# Power.net
KiCad netlist of a schematic drawn in Altium Designer
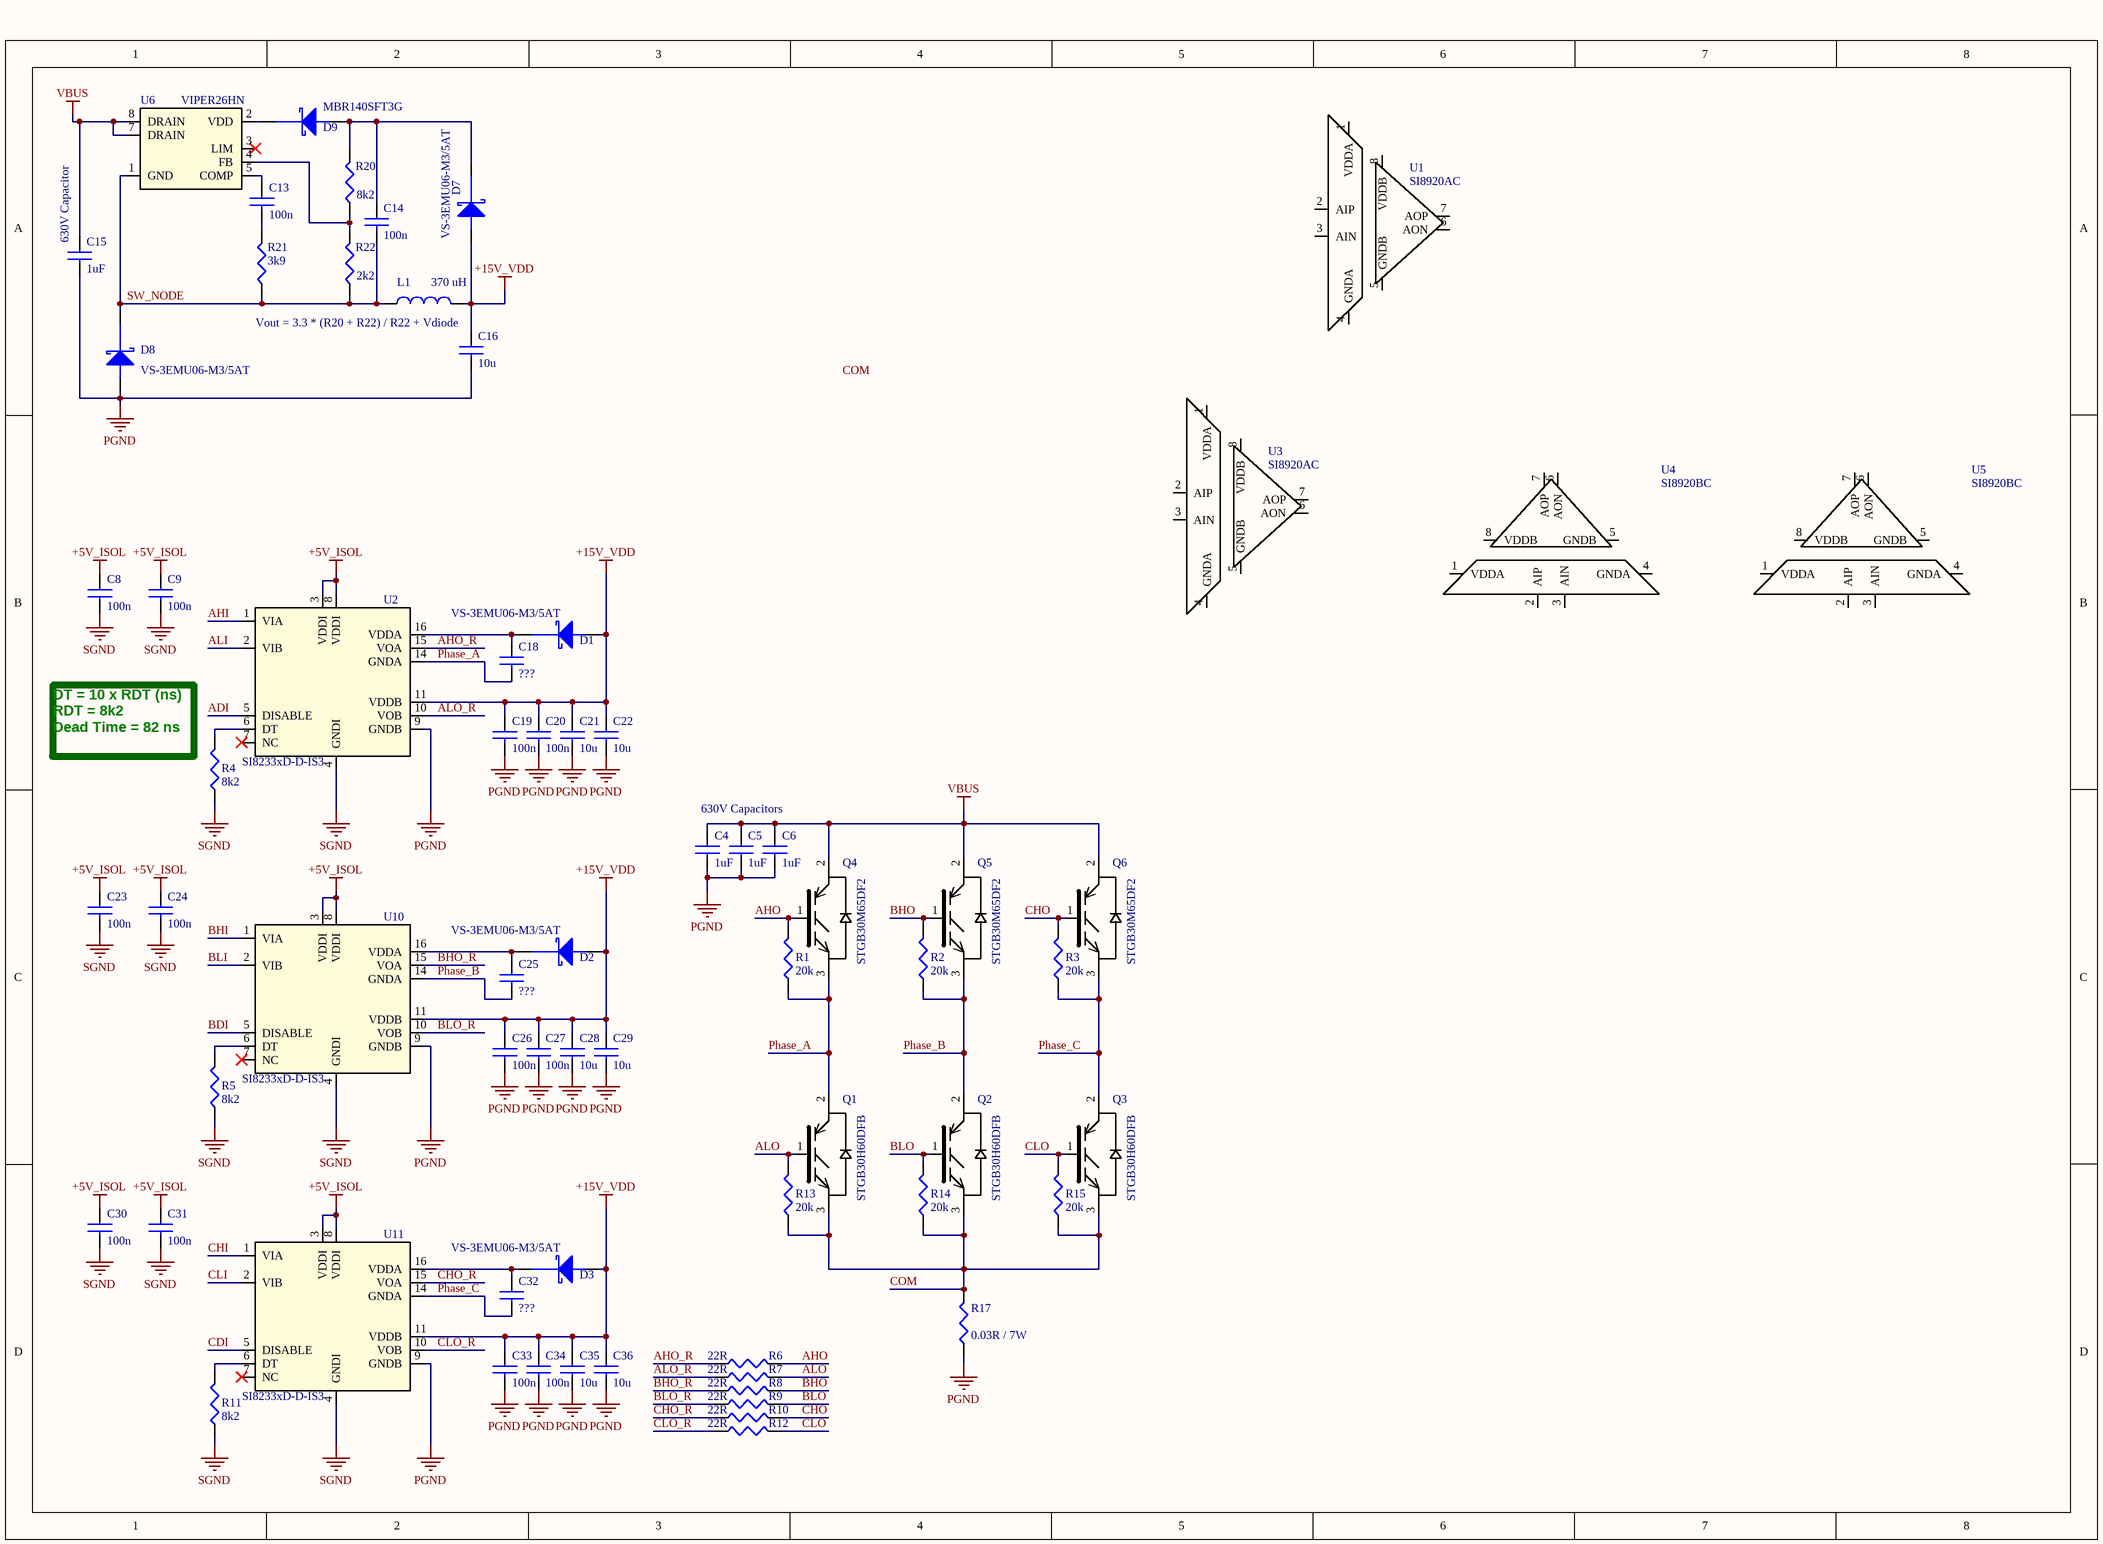
[diagram p0: Power.SchDoc]

(export (version "E")
  (design (tool "Eeschema 10.0.6"))
  (components
    (comp (ref "C4")
      (value "1uF")
      (footprint "AllogicaDisk_PcbLib:C_HIGH_V")
      (description "CAP CER 1UF 630V X7T STACKED SMD")
      (fields
        (field (name "MANUFACTURER") "Murata Electronics North America")
        (field (name "MANUFACTURER PART NUMBER") "KC355TD7LQ105MV01K")
      )
      (libsource (lib "AllogicaDisk_SchLib") (part "CAP_HIGH_VOLAGE"))
    )
    (comp (ref "C5")
      (value "1uF")
      (footprint "AllogicaDisk_PcbLib:C_HIGH_V")
      (description "CAP CER 1UF 630V X7T STACKED SMD")
      (fields
        (field (name "MANUFACTURER") "Murata Electronics North America")
        (field (name "MANUFACTURER PART NUMBER") "KC355TD7LQ105MV01K")
      )
      (libsource (lib "AllogicaDisk_SchLib") (part "CAP_HIGH_VOLAGE"))
    )
    (comp (ref "C6")
      (value "1uF")
      (footprint "AllogicaDisk_PcbLib:C_HIGH_V")
      (description "CAP CER 1UF 630V X7T STACKED SMD")
      (fields
        (field (name "MANUFACTURER") "Murata Electronics North America")
        (field (name "MANUFACTURER PART NUMBER") "KC355TD7LQ105MV01K")
      )
      (libsource (lib "AllogicaDisk_SchLib") (part "CAP_HIGH_VOLAGE"))
    )
    (comp (ref "C8")
      (value "100n")
      (footprint "AllogicaDisk_PcbLib:C0805")
      (description "0805 Capacitor")
      (libsource (lib "AllogicaDisk_SchLib") (part "CAP_0805"))
    )
    (comp (ref "C9")
      (value "100n")
      (footprint "AllogicaDisk_PcbLib:C0805")
      (description "0805 Capacitor")
      (libsource (lib "AllogicaDisk_SchLib") (part "CAP_0805"))
    )
    (comp (ref "C13")
      (value "100n")
      (footprint "AllogicaDisk_PcbLib:C0805")
      (description "0805 Capacitor")
      (libsource (lib "AllogicaDisk_SchLib") (part "CAP_0805"))
    )
    (comp (ref "C14")
      (value "100n")
      (footprint "AllogicaDisk_PcbLib:C0805")
      (description "0805 Capacitor")
      (libsource (lib "AllogicaDisk_SchLib") (part "CAP_0805"))
    )
    (comp (ref "C15")
      (value "1uF")
      (footprint "AllogicaDisk_PcbLib:C_HIGH_V")
      (description "CAP CER 1UF 630V X7T STACKED SMD")
      (fields
        (field (name "MANUFACTURER") "Murata Electronics North America")
        (field (name "MANUFACTURER PART NUMBER") "KC355TD7LQ105MV01K")
      )
      (libsource (lib "AllogicaDisk_SchLib") (part "CAP_HIGH_VOLAGE"))
    )
    (comp (ref "C16")
      (value "10u")
      (footprint "AllogicaDisk_PcbLib:C1206")
      (description "CAP CER 10UF 35V X5R 1206")
      (fields (field (name "TOLERANCE") "±20%") (field (name "MANUFACTURER") "Murata"))
      (libsource (lib "AllogicaDisk_SchLib") (part "CAP_1206_10u"))
    )
    (comp (ref "C18")
      (value "???")
      (footprint "AllogicaDisk_PcbLib:C0805")
      (description "0805 Capacitor")
      (libsource (lib "AllogicaDisk_SchLib") (part "CAP_0805"))
    )
    (comp (ref "C19")
      (value "100n")
      (footprint "AllogicaDisk_PcbLib:C0805")
      (description "0805 Capacitor")
      (libsource (lib "AllogicaDisk_SchLib") (part "CAP_0805"))
    )
    (comp (ref "C20")
      (value "100n")
      (footprint "AllogicaDisk_PcbLib:C0805")
      (description "0805 Capacitor")
      (libsource (lib "AllogicaDisk_SchLib") (part "CAP_0805"))
    )
    (comp (ref "C21")
      (value "10u")
      (footprint "AllogicaDisk_PcbLib:C0805")
      (description "0805 Capacitor")
      (libsource (lib "AllogicaDisk_SchLib") (part "CAP_0805"))
    )
    (comp (ref "C22")
      (value "10u")
      (footprint "AllogicaDisk_PcbLib:C0805")
      (description "0805 Capacitor")
      (libsource (lib "AllogicaDisk_SchLib") (part "CAP_0805"))
    )
    (comp (ref "C23")
      (value "100n")
      (footprint "AllogicaDisk_PcbLib:C0805")
      (description "0805 Capacitor")
      (libsource (lib "AllogicaDisk_SchLib") (part "CAP_0805"))
    )
    (comp (ref "C24")
      (value "100n")
      (footprint "AllogicaDisk_PcbLib:C0805")
      (description "0805 Capacitor")
      (libsource (lib "AllogicaDisk_SchLib") (part "CAP_0805"))
    )
    (comp (ref "C25")
      (value "???")
      (footprint "AllogicaDisk_PcbLib:C0805")
      (description "0805 Capacitor")
      (libsource (lib "AllogicaDisk_SchLib") (part "CAP_0805"))
    )
    (comp (ref "C26")
      (value "100n")
      (footprint "AllogicaDisk_PcbLib:C0805")
      (description "0805 Capacitor")
      (libsource (lib "AllogicaDisk_SchLib") (part "CAP_0805"))
    )
    (comp (ref "C27")
      (value "100n")
      (footprint "AllogicaDisk_PcbLib:C0805")
      (description "0805 Capacitor")
      (libsource (lib "AllogicaDisk_SchLib") (part "CAP_0805"))
    )
    (comp (ref "C28")
      (value "10u")
      (footprint "AllogicaDisk_PcbLib:C0805")
      (description "0805 Capacitor")
      (libsource (lib "AllogicaDisk_SchLib") (part "CAP_0805"))
    )
    (comp (ref "C29")
      (value "10u")
      (footprint "AllogicaDisk_PcbLib:C0805")
      (description "0805 Capacitor")
      (libsource (lib "AllogicaDisk_SchLib") (part "CAP_0805"))
    )
    (comp (ref "C30")
      (value "100n")
      (footprint "AllogicaDisk_PcbLib:C0805")
      (description "0805 Capacitor")
      (libsource (lib "AllogicaDisk_SchLib") (part "CAP_0805"))
    )
    (comp (ref "C31")
      (value "100n")
      (footprint "AllogicaDisk_PcbLib:C0805")
      (description "0805 Capacitor")
      (libsource (lib "AllogicaDisk_SchLib") (part "CAP_0805"))
    )
    (comp (ref "C32")
      (value "???")
      (footprint "AllogicaDisk_PcbLib:C0805")
      (description "0805 Capacitor")
      (libsource (lib "AllogicaDisk_SchLib") (part "CAP_0805"))
    )
    (comp (ref "C33")
      (value "100n")
      (footprint "AllogicaDisk_PcbLib:C0805")
      (description "0805 Capacitor")
      (libsource (lib "AllogicaDisk_SchLib") (part "CAP_0805"))
    )
    (comp (ref "C34")
      (value "100n")
      (footprint "AllogicaDisk_PcbLib:C0805")
      (description "0805 Capacitor")
      (libsource (lib "AllogicaDisk_SchLib") (part "CAP_0805"))
    )
    (comp (ref "C35")
      (value "10u")
      (footprint "AllogicaDisk_PcbLib:C0805")
      (description "0805 Capacitor")
      (libsource (lib "AllogicaDisk_SchLib") (part "CAP_0805"))
    )
    (comp (ref "C36")
      (value "10u")
      (footprint "AllogicaDisk_PcbLib:C0805")
      (description "0805 Capacitor")
      (libsource (lib "AllogicaDisk_SchLib") (part "CAP_0805"))
    )
    (comp (ref "D1")
      (value "VS-3EMU06-M3/5AT")
      (footprint "AllogicaDisk_PcbLib:DO-214AC")
      (description "DIODE GEN PURP 600V 3A DO214AC")
      (fields (field (name "MANUFACTURER") "Vishay Semiconductor Diodes Division"))
      (libsource (lib "AllogicaDisk_SchLib") (part "VS-3EMU06-M3/5AT"))
    )
    (comp (ref "D2")
      (value "VS-3EMU06-M3/5AT")
      (footprint "AllogicaDisk_PcbLib:DO-214AC")
      (description "DIODE GEN PURP 600V 3A DO214AC")
      (fields (field (name "MANUFACTURER") "Vishay Semiconductor Diodes Division"))
      (libsource (lib "AllogicaDisk_SchLib") (part "VS-3EMU06-M3/5AT"))
    )
    (comp (ref "D3")
      (value "VS-3EMU06-M3/5AT")
      (footprint "AllogicaDisk_PcbLib:DO-214AC")
      (description "DIODE GEN PURP 600V 3A DO214AC")
      (fields (field (name "MANUFACTURER") "Vishay Semiconductor Diodes Division"))
      (libsource (lib "AllogicaDisk_SchLib") (part "VS-3EMU06-M3/5AT"))
    )
    (comp (ref "D7")
      (value "VS-3EMU06-M3/5AT")
      (footprint "AllogicaDisk_PcbLib:DO-214AC")
      (description "DIODE GEN PURP 600V 3A DO214AC")
      (fields (field (name "MANUFACTURER") "Vishay Semiconductor Diodes Division"))
      (libsource (lib "AllogicaDisk_SchLib") (part "VS-3EMU06-M3/5AT"))
    )
    (comp (ref "D8")
      (value "VS-3EMU06-M3/5AT")
      (footprint "AllogicaDisk_PcbLib:DO-214AC")
      (description "DIODE GEN PURP 600V 3A DO214AC")
      (fields (field (name "MANUFACTURER") "Vishay Semiconductor Diodes Division"))
      (libsource (lib "AllogicaDisk_SchLib") (part "VS-3EMU06-M3/5AT"))
    )
    (comp (ref "D9")
      (value "MBR140SFT3G")
      (footprint "AllogicaDisk_PcbLib:SOD-123FL")
      (description "DIODE SCHOTTKY 550mV @ 1A, 40V, SOD123L")
      (fields
        (field (name "MANUFACTURER") "ON Semiconductor")
        (field (name "MANUFACTURER PART NUMBER") "MBR140SFT1G")
      )
      (libsource (lib "AllogicaDisk_SchLib") (part "MBR140SFT3G"))
    )
    (comp (ref "L1")
      (value "370 uH")
      (footprint "AllogicaDisk_PcbLib:IND_370u")
      (description "390µH Shielded Wirewound Inductor 1.6A 680 mOhm Max Nonstandard")
      (fields
        (field (name "MANUFACTURER") "Bourns Inc.")
        (field (name "MANUFACTURER PART NUMBER") "PM127SH-391M-RC")
      )
      (libsource (lib "AllogicaDisk_SchLib") (part "IND_370u"))
    )
    (comp (ref "Q1")
      (value "STGB30H60DFB")
      (footprint "AllogicaDisk_PcbLib:D2PAK")
      (description "TRENCH GATE FIELD-STOP IGBT, HB")
      (fields (field (name "MANUFACTURER") "STMicroelectronics"))
      (libsource (lib "AllogicaDisk_SchLib") (part "STGB30H60DFB"))
    )
    (comp (ref "Q2")
      (value "STGB30H60DFB")
      (footprint "AllogicaDisk_PcbLib:D2PAK")
      (description "TRENCH GATE FIELD-STOP IGBT, HB")
      (fields (field (name "MANUFACTURER") "STMicroelectronics"))
      (libsource (lib "AllogicaDisk_SchLib") (part "STGB30H60DFB"))
    )
    (comp (ref "Q3")
      (value "STGB30H60DFB")
      (footprint "AllogicaDisk_PcbLib:D2PAK")
      (description "TRENCH GATE FIELD-STOP IGBT, HB")
      (fields (field (name "MANUFACTURER") "STMicroelectronics"))
      (libsource (lib "AllogicaDisk_SchLib") (part "STGB30H60DFB"))
    )
    (comp (ref "Q4")
      (value "STGB30M65DF2")
      (footprint "AllogicaDisk_PcbLib:D2PAK")
      (description "IGBT 650V 30A D2PAK")
      (fields (field (name "MANUFACTURER") "STMicroelectronics"))
      (libsource (lib "AllogicaDisk_SchLib") (part "STGB30M65DF2"))
    )
    (comp (ref "Q5")
      (value "STGB30M65DF2")
      (footprint "AllogicaDisk_PcbLib:D2PAK")
      (description "IGBT 650V 30A D2PAK")
      (fields (field (name "MANUFACTURER") "STMicroelectronics"))
      (libsource (lib "AllogicaDisk_SchLib") (part "STGB30M65DF2"))
    )
    (comp (ref "Q6")
      (value "STGB30M65DF2")
      (footprint "AllogicaDisk_PcbLib:D2PAK")
      (description "IGBT 650V 30A D2PAK")
      (fields (field (name "MANUFACTURER") "STMicroelectronics"))
      (libsource (lib "AllogicaDisk_SchLib") (part "STGB30M65DF2"))
    )
    (comp (ref "R1")
      (value "20k")
      (footprint "AllogicaDisk_PcbLib:R0805")
      (libsource (lib "AllogicaDisk_SchLib") (part "RES_0805"))
    )
    (comp (ref "R2")
      (value "20k")
      (footprint "AllogicaDisk_PcbLib:R0805")
      (libsource (lib "AllogicaDisk_SchLib") (part "RES_0805"))
    )
    (comp (ref "R3")
      (value "20k")
      (footprint "AllogicaDisk_PcbLib:R0805")
      (libsource (lib "AllogicaDisk_SchLib") (part "RES_0805"))
    )
    (comp (ref "R4")
      (value "8k2")
      (footprint "AllogicaDisk_PcbLib:R0805")
      (libsource (lib "AllogicaDisk_SchLib") (part "RES_0805"))
    )
    (comp (ref "R5")
      (value "8k2")
      (footprint "AllogicaDisk_PcbLib:R0805")
      (libsource (lib "AllogicaDisk_SchLib") (part "RES_0805"))
    )
    (comp (ref "R6")
      (value "22R")
      (footprint "AllogicaDisk_PcbLib:R0805")
      (libsource (lib "AllogicaDisk_SchLib") (part "RES_0805"))
    )
    (comp (ref "R7")
      (value "22R")
      (footprint "AllogicaDisk_PcbLib:R0805")
      (libsource (lib "AllogicaDisk_SchLib") (part "RES_0805"))
    )
    (comp (ref "R8")
      (value "22R")
      (footprint "AllogicaDisk_PcbLib:R0805")
      (libsource (lib "AllogicaDisk_SchLib") (part "RES_0805"))
    )
    (comp (ref "R9")
      (value "22R")
      (footprint "AllogicaDisk_PcbLib:R0805")
      (libsource (lib "AllogicaDisk_SchLib") (part "RES_0805"))
    )
    (comp (ref "R10")
      (value "22R")
      (footprint "AllogicaDisk_PcbLib:R0805")
      (libsource (lib "AllogicaDisk_SchLib") (part "RES_0805"))
    )
    (comp (ref "R11")
      (value "8k2")
      (footprint "AllogicaDisk_PcbLib:R0805")
      (libsource (lib "AllogicaDisk_SchLib") (part "RES_0805"))
    )
    (comp (ref "R12")
      (value "22R")
      (footprint "AllogicaDisk_PcbLib:R0805")
      (libsource (lib "AllogicaDisk_SchLib") (part "RES_0805"))
    )
    (comp (ref "R13")
      (value "20k")
      (footprint "AllogicaDisk_PcbLib:R0805")
      (libsource (lib "AllogicaDisk_SchLib") (part "RES_0805"))
    )
    (comp (ref "R14")
      (value "20k")
      (footprint "AllogicaDisk_PcbLib:R0805")
      (libsource (lib "AllogicaDisk_SchLib") (part "RES_0805"))
    )
    (comp (ref "R15")
      (value "20k")
      (footprint "AllogicaDisk_PcbLib:R0805")
      (libsource (lib "AllogicaDisk_SchLib") (part "RES_0805"))
    )
    (comp (ref "R17")
      (value "0.03R / 7W")
      (footprint "AllogicaDisk_PcbLib:R2818")
      (description "RES 0.003 OHM 1% 7W 2818")
      (fields
        (field (name "MANUFACTURER") "Vishay Dale")
        (field (name "MANUFACTURER PART NUMBER") "WSHM28183L000FEA")
      )
      (libsource (lib "AllogicaDisk_SchLib") (part "res_2818"))
    )
    (comp (ref "R20")
      (value "8k2")
      (footprint "AllogicaDisk_PcbLib:R0805")
      (libsource (lib "AllogicaDisk_SchLib") (part "RES_0805"))
    )
    (comp (ref "R21")
      (value "3k9")
      (footprint "AllogicaDisk_PcbLib:R0805")
      (libsource (lib "AllogicaDisk_SchLib") (part "RES_0805"))
    )
    (comp (ref "R22")
      (value "2k2")
      (footprint "AllogicaDisk_PcbLib:R0805")
      (libsource (lib "AllogicaDisk_SchLib") (part "RES_0805"))
    )
    (comp (ref "U1")
      (value "SI8920AC")
      (footprint "AllogicaDisk_PcbLib:8_DIP_SMD")
      (description "IC OP AMP ISOLATION 8DIP-GW")
      (fields
        (field (name "MANUFACTURER") "Silicon Labs")
        (field (name "MANUFACTURER PART NUMBER") "SI8920AC-IP")
      )
      (libsource (lib "AllogicaDisk_SchLib") (part "SI8920AC"))
    )
    (comp (ref "U2")
      (value "SI8233xD-D-IS3")
      (footprint "AllogicaDisk_PcbLib:SOIC-16 Wide (14-pins)")
      (description "ISOLATED GATE DRIVER, 8 MM CREEP")
      (fields
        (field (name "MANUFACTURER") "Silicon Labs")
        (field (name "MANUFACTURER PART NUMBER") "SI8233AD-D-IS3")
      )
      (libsource (lib "AllogicaDisk_SchLib") (part "SI8233xD-D-IS3"))
    )
    (comp (ref "U3")
      (value "SI8920AC")
      (footprint "AllogicaDisk_PcbLib:8_DIP_SMD")
      (description "IC OP AMP ISOLATION 8DIP-GW")
      (fields
        (field (name "MANUFACTURER") "Silicon Labs")
        (field (name "MANUFACTURER PART NUMBER") "SI8920AC-IP")
      )
      (libsource (lib "AllogicaDisk_SchLib") (part "SI8920AC"))
    )
    (comp (ref "U4")
      (value "SI8920BC")
      (footprint "AllogicaDisk_PcbLib:8_DIP_SMD")
      (description "IC OP AMP ISOLATION 8DIP-GW")
      (fields
        (field (name "MANUFACTURER") "Silicon Labs")
        (field (name "MANUFACTURER PART NUMBER") "SI8920BC-IP")
      )
      (libsource (lib "AllogicaDisk_SchLib") (part "SI8920BC"))
    )
    (comp (ref "U5")
      (value "SI8920BC")
      (footprint "AllogicaDisk_PcbLib:8_DIP_SMD")
      (description "IC OP AMP ISOLATION 8DIP-GW")
      (fields
        (field (name "MANUFACTURER") "Silicon Labs")
        (field (name "MANUFACTURER PART NUMBER") "SI8920BC-IP")
      )
      (libsource (lib "AllogicaDisk_SchLib") (part "SI8920BC"))
    )
    (comp (ref "U6")
      (value "VIPER26HN")
      (footprint "AllogicaDisk_PcbLib:7_DIP")
      (description "IC OFFLINE CONV PWM 800V 7-DIP")
      (fields (field (name "MANUFACTURER") "STMicroelectronics") (field (name "BASE PART NUMBER") "VIPER26"))
      (libsource (lib "AllogicaDisk_SchLib") (part "VIPER26HN"))
    )
    (comp (ref "U10")
      (value "SI8233xD-D-IS3")
      (footprint "AllogicaDisk_PcbLib:SOIC-16 Wide (14-pins)")
      (description "ISOLATED GATE DRIVER, 8 MM CREEP")
      (fields
        (field (name "MANUFACTURER") "Silicon Labs")
        (field (name "MANUFACTURER PART NUMBER") "SI8233AD-D-IS3")
      )
      (libsource (lib "AllogicaDisk_SchLib") (part "SI8233xD-D-IS3"))
    )
    (comp (ref "U11")
      (value "SI8233xD-D-IS3")
      (footprint "AllogicaDisk_PcbLib:SOIC-16 Wide (14-pins)")
      (description "ISOLATED GATE DRIVER, 8 MM CREEP")
      (fields
        (field (name "MANUFACTURER") "Silicon Labs")
        (field (name "MANUFACTURER PART NUMBER") "SI8233AD-D-IS3")
      )
      (libsource (lib "AllogicaDisk_SchLib") (part "SI8233xD-D-IS3"))
    )
  )
  (nets
    (net (code "1") (name "+5V_ISOL") (class "Default")
      (node (ref "C23") (pin "1") (pinfunction "1_1") (pintype "passive"))
      (node (ref "C24") (pin "1") (pinfunction "1_1") (pintype "passive"))
      (node (ref "C30") (pin "1") (pinfunction "1_1") (pintype "passive"))
      (node (ref "C31") (pin "1") (pinfunction "1_1") (pintype "passive"))
      (node (ref "C8") (pin "1") (pinfunction "1_1") (pintype "passive"))
      (node (ref "C9") (pin "1") (pinfunction "1_1") (pintype "passive"))
      (node (ref "U10") (pin "3") (pinfunction "VDDI_3") (pintype "passive"))
      (node (ref "U10") (pin "8") (pinfunction "VDDI_8") (pintype "passive"))
      (node (ref "U11") (pin "3") (pinfunction "VDDI_3") (pintype "passive"))
      (node (ref "U11") (pin "8") (pinfunction "VDDI_8") (pintype "passive"))
      (node (ref "U2") (pin "3") (pinfunction "VDDI_3") (pintype "passive"))
      (node (ref "U2") (pin "8") (pinfunction "VDDI_8") (pintype "passive"))
    )
    (net (code "2") (name "+15V_VDD") (class "Default")
      (node (ref "C16") (pin "1") (pinfunction "1_1") (pintype "passive"))
      (node (ref "C19") (pin "1") (pinfunction "1_1") (pintype "passive"))
      (node (ref "C20") (pin "1") (pinfunction "1_1") (pintype "passive"))
      (node (ref "C21") (pin "1") (pinfunction "1_1") (pintype "passive"))
      (node (ref "C22") (pin "1") (pinfunction "1_1") (pintype "passive"))
      (node (ref "C26") (pin "1") (pinfunction "1_1") (pintype "passive"))
      (node (ref "C27") (pin "1") (pinfunction "1_1") (pintype "passive"))
      (node (ref "C28") (pin "1") (pinfunction "1_1") (pintype "passive"))
      (node (ref "C29") (pin "1") (pinfunction "1_1") (pintype "passive"))
      (node (ref "C33") (pin "1") (pinfunction "1_1") (pintype "passive"))
      (node (ref "C34") (pin "1") (pinfunction "1_1") (pintype "passive"))
      (node (ref "C35") (pin "1") (pinfunction "1_1") (pintype "passive"))
      (node (ref "C36") (pin "1") (pinfunction "1_1") (pintype "passive"))
      (node (ref "D1") (pin "2") (pinfunction "Anode_2") (pintype "passive"))
      (node (ref "D2") (pin "2") (pinfunction "Anode_2") (pintype "passive"))
      (node (ref "D3") (pin "2") (pinfunction "Anode_2") (pintype "passive"))
      (node (ref "D7") (pin "2") (pinfunction "Anode_2") (pintype "passive"))
      (node (ref "L1") (pin "2") (pinfunction "2_2") (pintype "passive"))
      (node (ref "U10") (pin "11") (pinfunction "VDDB_11") (pintype "passive"))
      (node (ref "U11") (pin "11") (pinfunction "VDDB_11") (pintype "passive"))
      (node (ref "U2") (pin "11") (pinfunction "VDDB_11") (pintype "passive"))
    )
    (net (code "3") (name "/ADI") (class "Default")
      (node (ref "U2") (pin "5") (pinfunction "DISABLE_5") (pintype "passive"))
    )
    (net (code "4") (name "/AHI") (class "Default")
      (node (ref "U2") (pin "1") (pinfunction "VIA_1") (pintype "passive"))
    )
    (net (code "5") (name "/AHO") (class "Default")
      (node (ref "Q4") (pin "1") (pinfunction "GATE_1") (pintype "passive"))
      (node (ref "R1") (pin "2") (pinfunction "2_2") (pintype "passive"))
      (node (ref "R6") (pin "2") (pinfunction "2_2") (pintype "passive"))
    )
    (net (code "6") (name "/AHO_R") (class "Default")
      (node (ref "R6") (pin "1") (pinfunction "1_1") (pintype "passive"))
      (node (ref "U2") (pin "15") (pinfunction "VOA_15") (pintype "passive"))
    )
    (net (code "7") (name "/ALI") (class "Default")
      (node (ref "U2") (pin "2") (pinfunction "VIB_2") (pintype "passive"))
    )
    (net (code "8") (name "/ALO") (class "Default")
      (node (ref "Q1") (pin "1") (pinfunction "GATE_1") (pintype "passive"))
      (node (ref "R13") (pin "2") (pinfunction "2_2") (pintype "passive"))
      (node (ref "R7") (pin "2") (pinfunction "2_2") (pintype "passive"))
    )
    (net (code "9") (name "/ALO_R") (class "Default")
      (node (ref "R7") (pin "1") (pinfunction "1_1") (pintype "passive"))
      (node (ref "U2") (pin "10") (pinfunction "VOB_10") (pintype "passive"))
    )
    (net (code "10") (name "/BDI") (class "Default")
      (node (ref "U10") (pin "5") (pinfunction "DISABLE_5") (pintype "passive"))
    )
    (net (code "11") (name "/BHI") (class "Default")
      (node (ref "U10") (pin "1") (pinfunction "VIA_1") (pintype "passive"))
    )
    (net (code "12") (name "/BHO") (class "Default")
      (node (ref "Q5") (pin "1") (pinfunction "GATE_1") (pintype "passive"))
      (node (ref "R2") (pin "2") (pinfunction "2_2") (pintype "passive"))
      (node (ref "R8") (pin "2") (pinfunction "2_2") (pintype "passive"))
    )
    (net (code "13") (name "/BHO_R") (class "Default")
      (node (ref "R8") (pin "1") (pinfunction "1_1") (pintype "passive"))
      (node (ref "U10") (pin "15") (pinfunction "VOA_15") (pintype "passive"))
    )
    (net (code "14") (name "/BLI") (class "Default")
      (node (ref "U10") (pin "2") (pinfunction "VIB_2") (pintype "passive"))
    )
    (net (code "15") (name "/BLO") (class "Default")
      (node (ref "Q2") (pin "1") (pinfunction "GATE_1") (pintype "passive"))
      (node (ref "R14") (pin "2") (pinfunction "2_2") (pintype "passive"))
      (node (ref "R9") (pin "2") (pinfunction "2_2") (pintype "passive"))
    )
    (net (code "16") (name "/BLO_R") (class "Default")
      (node (ref "R9") (pin "1") (pinfunction "1_1") (pintype "passive"))
      (node (ref "U10") (pin "10") (pinfunction "VOB_10") (pintype "passive"))
    )
    (net (code "17") (name "/CDI") (class "Default")
      (node (ref "U11") (pin "5") (pinfunction "DISABLE_5") (pintype "passive"))
    )
    (net (code "18") (name "/CHI") (class "Default")
      (node (ref "U11") (pin "1") (pinfunction "VIA_1") (pintype "passive"))
    )
    (net (code "19") (name "/CHO") (class "Default")
      (node (ref "Q6") (pin "1") (pinfunction "GATE_1") (pintype "passive"))
      (node (ref "R10") (pin "2") (pinfunction "2_2") (pintype "passive"))
      (node (ref "R3") (pin "2") (pinfunction "2_2") (pintype "passive"))
    )
    (net (code "20") (name "/CHO_R") (class "Default")
      (node (ref "R10") (pin "1") (pinfunction "1_1") (pintype "passive"))
      (node (ref "U11") (pin "15") (pinfunction "VOA_15") (pintype "passive"))
    )
    (net (code "21") (name "/CLI") (class "Default")
      (node (ref "U11") (pin "2") (pinfunction "VIB_2") (pintype "passive"))
    )
    (net (code "22") (name "/CLO") (class "Default")
      (node (ref "Q3") (pin "1") (pinfunction "GATE_1") (pintype "passive"))
      (node (ref "R12") (pin "2") (pinfunction "2_2") (pintype "passive"))
      (node (ref "R15") (pin "2") (pinfunction "2_2") (pintype "passive"))
    )
    (net (code "23") (name "/CLO_R") (class "Default")
      (node (ref "R12") (pin "1") (pinfunction "1_1") (pintype "passive"))
      (node (ref "U11") (pin "10") (pinfunction "VOB_10") (pintype "passive"))
    )
    (net (code "24") (name "/COM") (class "Default")
      (node (ref "Q1") (pin "3") (pinfunction "SOURCE_3") (pintype "passive"))
      (node (ref "Q2") (pin "3") (pinfunction "SOURCE_3") (pintype "passive"))
      (node (ref "Q3") (pin "3") (pinfunction "SOURCE_3") (pintype "passive"))
      (node (ref "R13") (pin "1") (pinfunction "1_1") (pintype "passive"))
      (node (ref "R14") (pin "1") (pinfunction "1_1") (pintype "passive"))
      (node (ref "R15") (pin "1") (pinfunction "1_1") (pintype "passive"))
      (node (ref "R17") (pin "2") (pinfunction "2_2") (pintype "passive"))
    )
    (net (code "25") (name "/Phase_A") (class "Default")
      (node (ref "C18") (pin "2") (pinfunction "2_2") (pintype "passive"))
      (node (ref "Q1") (pin "2") (pinfunction "DRAIN_2") (pintype "passive"))
      (node (ref "Q4") (pin "3") (pinfunction "SOURCE_3") (pintype "passive"))
      (node (ref "R1") (pin "1") (pinfunction "1_1") (pintype "passive"))
      (node (ref "U2") (pin "14") (pinfunction "GNDA_14") (pintype "passive"))
    )
    (net (code "26") (name "/Phase_B") (class "Default")
      (node (ref "C25") (pin "2") (pinfunction "2_2") (pintype "passive"))
      (node (ref "Q2") (pin "2") (pinfunction "DRAIN_2") (pintype "passive"))
      (node (ref "Q5") (pin "3") (pinfunction "SOURCE_3") (pintype "passive"))
      (node (ref "R2") (pin "1") (pinfunction "1_1") (pintype "passive"))
      (node (ref "U10") (pin "14") (pinfunction "GNDA_14") (pintype "passive"))
    )
    (net (code "27") (name "/Phase_C") (class "Default")
      (node (ref "C32") (pin "2") (pinfunction "2_2") (pintype "passive"))
      (node (ref "Q3") (pin "2") (pinfunction "DRAIN_2") (pintype "passive"))
      (node (ref "Q6") (pin "3") (pinfunction "SOURCE_3") (pintype "passive"))
      (node (ref "R3") (pin "1") (pinfunction "1_1") (pintype "passive"))
      (node (ref "U11") (pin "14") (pinfunction "GNDA_14") (pintype "passive"))
    )
    (net (code "28") (name "/SW_NODE") (class "Default")
      (node (ref "C14") (pin "2") (pinfunction "2_2") (pintype "passive"))
      (node (ref "D8") (pin "1") (pinfunction "Cathode_1") (pintype "passive"))
      (node (ref "L1") (pin "1") (pinfunction "1_1") (pintype "passive"))
      (node (ref "R21") (pin "1") (pinfunction "1_1") (pintype "passive"))
      (node (ref "R22") (pin "1") (pinfunction "1_1") (pintype "passive"))
      (node (ref "U6") (pin "1") (pinfunction "GND_1") (pintype "passive"))
    )
    (net (code "29") (name "Net-(C13-Pad2)") (class "Default")
      (node (ref "C13") (pin "2") (pinfunction "2_2") (pintype "passive"))
      (node (ref "R21") (pin "2") (pinfunction "2_2") (pintype "passive"))
    )
    (net (code "30") (name "Net-(D1-Cathode)") (class "Default")
      (node (ref "C18") (pin "1") (pinfunction "1_1") (pintype "passive"))
      (node (ref "D1") (pin "1") (pinfunction "Cathode_1") (pintype "passive"))
      (node (ref "U2") (pin "16") (pinfunction "VDDA_16") (pintype "passive"))
    )
    (net (code "31") (name "Net-(D2-Cathode)") (class "Default")
      (node (ref "C25") (pin "1") (pinfunction "1_1") (pintype "passive"))
      (node (ref "D2") (pin "1") (pinfunction "Cathode_1") (pintype "passive"))
      (node (ref "U10") (pin "16") (pinfunction "VDDA_16") (pintype "passive"))
    )
    (net (code "32") (name "Net-(D3-Cathode)") (class "Default")
      (node (ref "C32") (pin "1") (pinfunction "1_1") (pintype "passive"))
      (node (ref "D3") (pin "1") (pinfunction "Cathode_1") (pintype "passive"))
      (node (ref "U11") (pin "16") (pinfunction "VDDA_16") (pintype "passive"))
    )
    (net (code "33") (name "Net-(D7-Cathode)") (class "Default")
      (node (ref "C14") (pin "1") (pinfunction "1_1") (pintype "passive"))
      (node (ref "D7") (pin "1") (pinfunction "Cathode_1") (pintype "passive"))
      (node (ref "D9") (pin "2") (pinfunction "Anode_2") (pintype "passive"))
      (node (ref "R20") (pin "2") (pinfunction "2_2") (pintype "passive"))
    )
    (net (code "34") (name "Net-(D9-Cathode)") (class "Default")
      (node (ref "D9") (pin "1") (pinfunction "Cathode_1") (pintype "passive"))
      (node (ref "U6") (pin "2") (pinfunction "VDD_2") (pintype "passive"))
    )
    (net (code "35") (name "Net-(U2-DT)") (class "Default")
      (node (ref "R4") (pin "2") (pinfunction "2_2") (pintype "passive"))
      (node (ref "U2") (pin "6") (pinfunction "DT_6") (pintype "passive"))
    )
    (net (code "36") (name "Net-(U6-COMP)") (class "Default")
      (node (ref "C13") (pin "1") (pinfunction "1_1") (pintype "passive"))
      (node (ref "U6") (pin "5") (pinfunction "COMP_5") (pintype "passive"))
    )
    (net (code "37") (name "Net-(U6-FB)") (class "Default")
      (node (ref "R20") (pin "1") (pinfunction "1_1") (pintype "passive"))
      (node (ref "R22") (pin "2") (pinfunction "2_2") (pintype "passive"))
      (node (ref "U6") (pin "4") (pinfunction "FB_4") (pintype "passive"))
    )
    (net (code "38") (name "Net-(U10-DT)") (class "Default")
      (node (ref "R5") (pin "2") (pinfunction "2_2") (pintype "passive"))
      (node (ref "U10") (pin "6") (pinfunction "DT_6") (pintype "passive"))
    )
    (net (code "39") (name "Net-(U11-DT)") (class "Default")
      (node (ref "R11") (pin "2") (pinfunction "2_2") (pintype "passive"))
      (node (ref "U11") (pin "6") (pinfunction "DT_6") (pintype "passive"))
    )
    (net (code "40") (name "PGND") (class "Default")
      (node (ref "C15") (pin "2") (pinfunction "2_2") (pintype "passive"))
      (node (ref "C16") (pin "2") (pinfunction "2_2") (pintype "passive"))
      (node (ref "C19") (pin "2") (pinfunction "2_2") (pintype "passive"))
      (node (ref "C20") (pin "2") (pinfunction "2_2") (pintype "passive"))
      (node (ref "C21") (pin "2") (pinfunction "2_2") (pintype "passive"))
      (node (ref "C22") (pin "2") (pinfunction "2_2") (pintype "passive"))
      (node (ref "C26") (pin "2") (pinfunction "2_2") (pintype "passive"))
      (node (ref "C27") (pin "2") (pinfunction "2_2") (pintype "passive"))
      (node (ref "C28") (pin "2") (pinfunction "2_2") (pintype "passive"))
      (node (ref "C29") (pin "2") (pinfunction "2_2") (pintype "passive"))
      (node (ref "C33") (pin "2") (pinfunction "2_2") (pintype "passive"))
      (node (ref "C34") (pin "2") (pinfunction "2_2") (pintype "passive"))
      (node (ref "C35") (pin "2") (pinfunction "2_2") (pintype "passive"))
      (node (ref "C36") (pin "2") (pinfunction "2_2") (pintype "passive"))
      (node (ref "C4") (pin "2") (pinfunction "2_2") (pintype "passive"))
      (node (ref "C5") (pin "2") (pinfunction "2_2") (pintype "passive"))
      (node (ref "C6") (pin "2") (pinfunction "2_2") (pintype "passive"))
      (node (ref "D8") (pin "2") (pinfunction "Anode_2") (pintype "passive"))
      (node (ref "R17") (pin "1") (pinfunction "1_1") (pintype "passive"))
      (node (ref "U10") (pin "9") (pinfunction "GNDB_9") (pintype "passive"))
      (node (ref "U11") (pin "9") (pinfunction "GNDB_9") (pintype "passive"))
      (node (ref "U2") (pin "9") (pinfunction "GNDB_9") (pintype "passive"))
    )
    (net (code "41") (name "SGND") (class "Default")
      (node (ref "C23") (pin "2") (pinfunction "2_2") (pintype "passive"))
      (node (ref "C24") (pin "2") (pinfunction "2_2") (pintype "passive"))
      (node (ref "C30") (pin "2") (pinfunction "2_2") (pintype "passive"))
      (node (ref "C31") (pin "2") (pinfunction "2_2") (pintype "passive"))
      (node (ref "C8") (pin "2") (pinfunction "2_2") (pintype "passive"))
      (node (ref "C9") (pin "2") (pinfunction "2_2") (pintype "passive"))
      (node (ref "R11") (pin "1") (pinfunction "1_1") (pintype "passive"))
      (node (ref "R4") (pin "1") (pinfunction "1_1") (pintype "passive"))
      (node (ref "R5") (pin "1") (pinfunction "1_1") (pintype "passive"))
      (node (ref "U10") (pin "4") (pinfunction "GNDI_4") (pintype "passive"))
      (node (ref "U11") (pin "4") (pinfunction "GNDI_4") (pintype "passive"))
      (node (ref "U2") (pin "4") (pinfunction "GNDI_4") (pintype "passive"))
    )
    (net (code "42") (name "VBUS") (class "Default")
      (node (ref "C15") (pin "1") (pinfunction "1_1") (pintype "passive"))
      (node (ref "C4") (pin "1") (pinfunction "1_1") (pintype "passive"))
      (node (ref "C5") (pin "1") (pinfunction "1_1") (pintype "passive"))
      (node (ref "C6") (pin "1") (pinfunction "1_1") (pintype "passive"))
      (node (ref "Q4") (pin "2") (pinfunction "DRAIN_2") (pintype "passive"))
      (node (ref "Q5") (pin "2") (pinfunction "DRAIN_2") (pintype "passive"))
      (node (ref "Q6") (pin "2") (pinfunction "DRAIN_2") (pintype "passive"))
      (node (ref "U6") (pin "7") (pinfunction "DRAIN_7") (pintype "passive"))
      (node (ref "U6") (pin "8") (pinfunction "DRAIN_8") (pintype "passive"))
    )
    (net (code "43") (name "unconnected-(U1-AIN-Pad3)") (class "Default")
      (node (ref "U1") (pin "3") (pinfunction "AIN_3") (pintype "passive"))
    )
    (net (code "44") (name "unconnected-(U1-AIP-Pad2)") (class "Default")
      (node (ref "U1") (pin "2") (pinfunction "AIP_2") (pintype "passive"))
    )
    (net (code "45") (name "unconnected-(U1-AON-Pad6)") (class "Default")
      (node (ref "U1") (pin "6") (pinfunction "AON_6") (pintype "passive"))
    )
    (net (code "46") (name "unconnected-(U1-AOP-Pad7)") (class "Default")
      (node (ref "U1") (pin "7") (pinfunction "AOP_7") (pintype "passive"))
    )
    (net (code "47") (name "unconnected-(U1-GNDA-Pad4)") (class "Default")
      (node (ref "U1") (pin "4") (pinfunction "GNDA_4") (pintype "passive"))
    )
    (net (code "48") (name "unconnected-(U1-GNDB-Pad5)") (class "Default")
      (node (ref "U1") (pin "5") (pinfunction "GNDB_5") (pintype "passive"))
    )
    (net (code "49") (name "unconnected-(U1-VDDA-Pad1)") (class "Default")
      (node (ref "U1") (pin "1") (pinfunction "VDDA_1") (pintype "passive"))
    )
    (net (code "50") (name "unconnected-(U1-VDDB-Pad8)") (class "Default")
      (node (ref "U1") (pin "8") (pinfunction "VDDB_8") (pintype "passive"))
    )
    (net (code "51") (name "unconnected-(U2-NC-Pad7)") (class "Default")
      (node (ref "U2") (pin "7") (pinfunction "NC_7") (pintype "passive+no_connect"))
    )
    (net (code "52") (name "unconnected-(U3-AIN-Pad3)") (class "Default")
      (node (ref "U3") (pin "3") (pinfunction "AIN_3") (pintype "passive"))
    )
    (net (code "53") (name "unconnected-(U3-AIP-Pad2)") (class "Default")
      (node (ref "U3") (pin "2") (pinfunction "AIP_2") (pintype "passive"))
    )
    (net (code "54") (name "unconnected-(U3-AON-Pad6)") (class "Default")
      (node (ref "U3") (pin "6") (pinfunction "AON_6") (pintype "passive"))
    )
    (net (code "55") (name "unconnected-(U3-AOP-Pad7)") (class "Default")
      (node (ref "U3") (pin "7") (pinfunction "AOP_7") (pintype "passive"))
    )
    (net (code "56") (name "unconnected-(U3-GNDA-Pad4)") (class "Default")
      (node (ref "U3") (pin "4") (pinfunction "GNDA_4") (pintype "passive"))
    )
    (net (code "57") (name "unconnected-(U3-GNDB-Pad5)") (class "Default")
      (node (ref "U3") (pin "5") (pinfunction "GNDB_5") (pintype "passive"))
    )
    (net (code "58") (name "unconnected-(U3-VDDA-Pad1)") (class "Default")
      (node (ref "U3") (pin "1") (pinfunction "VDDA_1") (pintype "passive"))
    )
    (net (code "59") (name "unconnected-(U3-VDDB-Pad8)") (class "Default")
      (node (ref "U3") (pin "8") (pinfunction "VDDB_8") (pintype "passive"))
    )
    (net (code "60") (name "unconnected-(U4-AIN-Pad3)") (class "Default")
      (node (ref "U4") (pin "3") (pinfunction "AIN_3") (pintype "passive"))
    )
    (net (code "61") (name "unconnected-(U4-AIP-Pad2)") (class "Default")
      (node (ref "U4") (pin "2") (pinfunction "AIP_2") (pintype "passive"))
    )
    (net (code "62") (name "unconnected-(U4-AON-Pad6)") (class "Default")
      (node (ref "U4") (pin "6") (pinfunction "AON_6") (pintype "passive"))
    )
    (net (code "63") (name "unconnected-(U4-AOP-Pad7)") (class "Default")
      (node (ref "U4") (pin "7") (pinfunction "AOP_7") (pintype "passive"))
    )
    (net (code "64") (name "unconnected-(U4-GNDA-Pad4)") (class "Default")
      (node (ref "U4") (pin "4") (pinfunction "GNDA_4") (pintype "passive"))
    )
    (net (code "65") (name "unconnected-(U4-GNDB-Pad5)") (class "Default")
      (node (ref "U4") (pin "5") (pinfunction "GNDB_5") (pintype "passive"))
    )
    (net (code "66") (name "unconnected-(U4-VDDA-Pad1)") (class "Default")
      (node (ref "U4") (pin "1") (pinfunction "VDDA_1") (pintype "passive"))
    )
    (net (code "67") (name "unconnected-(U4-VDDB-Pad8)") (class "Default")
      (node (ref "U4") (pin "8") (pinfunction "VDDB_8") (pintype "passive"))
    )
    (net (code "68") (name "unconnected-(U5-AIN-Pad3)") (class "Default")
      (node (ref "U5") (pin "3") (pinfunction "AIN_3") (pintype "passive"))
    )
    (net (code "69") (name "unconnected-(U5-AIP-Pad2)") (class "Default")
      (node (ref "U5") (pin "2") (pinfunction "AIP_2") (pintype "passive"))
    )
    (net (code "70") (name "unconnected-(U5-AON-Pad6)") (class "Default")
      (node (ref "U5") (pin "6") (pinfunction "AON_6") (pintype "passive"))
    )
    (net (code "71") (name "unconnected-(U5-AOP-Pad7)") (class "Default")
      (node (ref "U5") (pin "7") (pinfunction "AOP_7") (pintype "passive"))
    )
    (net (code "72") (name "unconnected-(U5-GNDA-Pad4)") (class "Default")
      (node (ref "U5") (pin "4") (pinfunction "GNDA_4") (pintype "passive"))
    )
    (net (code "73") (name "unconnected-(U5-GNDB-Pad5)") (class "Default")
      (node (ref "U5") (pin "5") (pinfunction "GNDB_5") (pintype "passive"))
    )
    (net (code "74") (name "unconnected-(U5-VDDA-Pad1)") (class "Default")
      (node (ref "U5") (pin "1") (pinfunction "VDDA_1") (pintype "passive"))
    )
    (net (code "75") (name "unconnected-(U5-VDDB-Pad8)") (class "Default")
      (node (ref "U5") (pin "8") (pinfunction "VDDB_8") (pintype "passive"))
    )
    (net (code "76") (name "unconnected-(U6-LIM-Pad3)") (class "Default")
      (node (ref "U6") (pin "3") (pinfunction "LIM_3") (pintype "passive+no_connect"))
    )
    (net (code "77") (name "unconnected-(U10-NC-Pad7)") (class "Default")
      (node (ref "U10") (pin "7") (pinfunction "NC_7") (pintype "passive+no_connect"))
    )
    (net (code "78") (name "unconnected-(U11-NC-Pad7)") (class "Default")
      (node (ref "U11") (pin "7") (pinfunction "NC_7") (pintype "passive+no_connect"))
    )
  )
)
